# POWER.net
KiCad netlist of a schematic drawn in Altium Designer
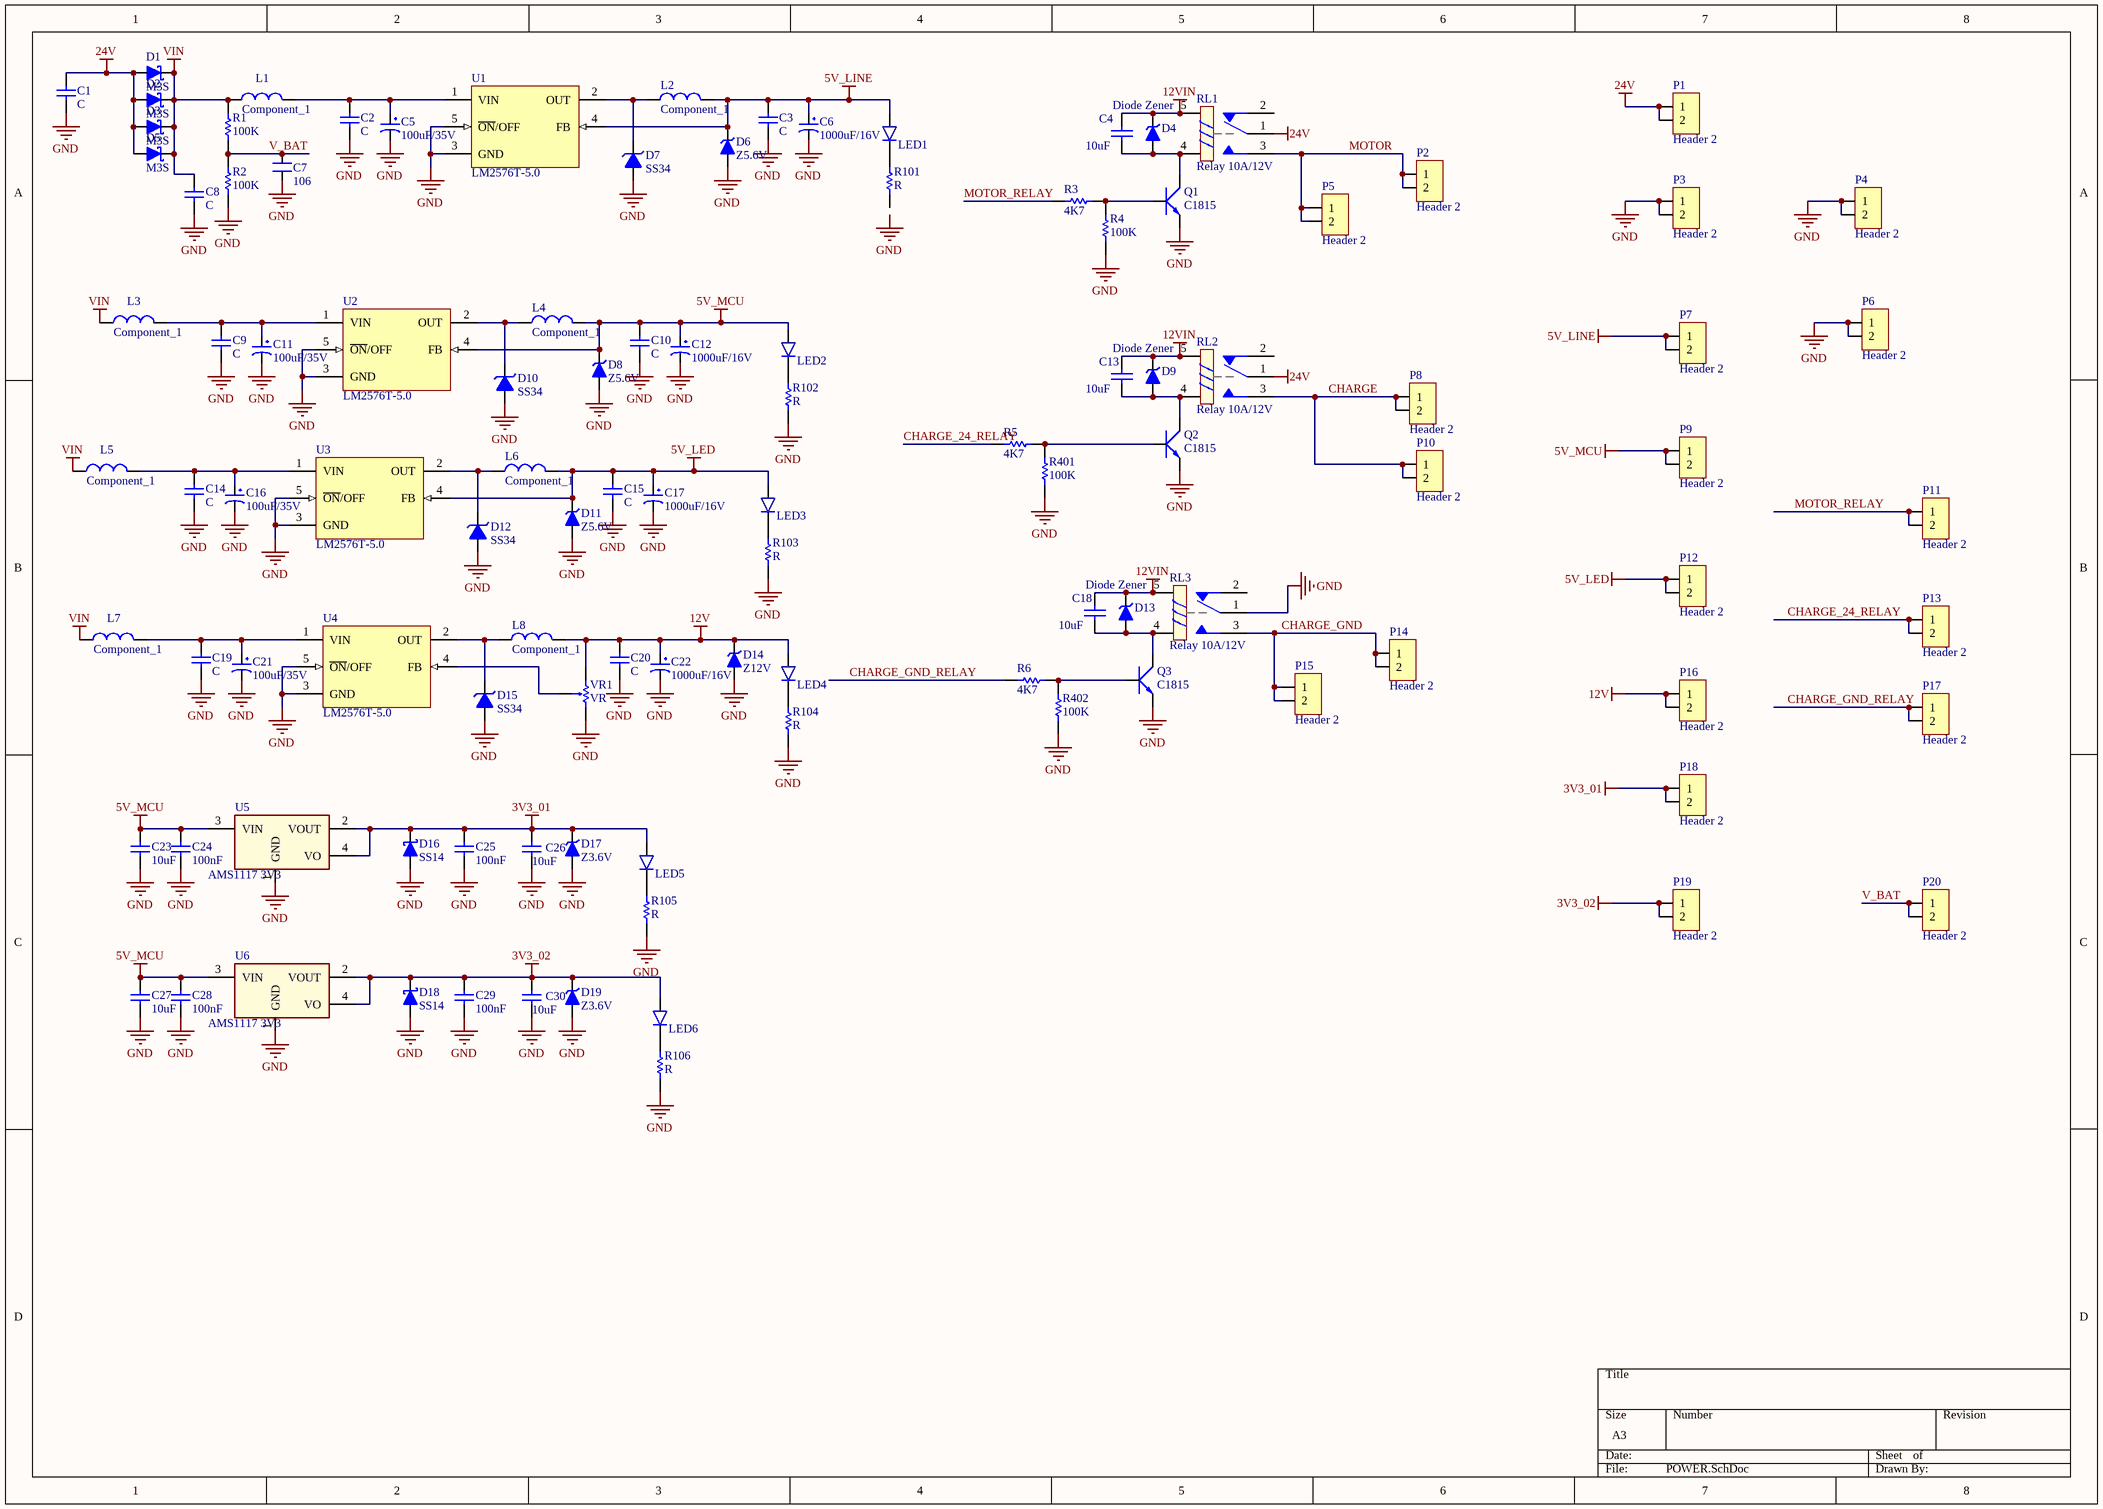
[diagram p0: POWER.SchDoc]

(export (version "E")
  (design (tool "Eeschema 10.0.6"))
  (components
    (comp (ref "C1")
      (value "C")
      (footprint "VARISTOR DISC 5MM/7MM")
      (description "Capacitor non-pol")
      (libsource (lib "BKIT4U_LIB") (part "Capacitor NP"))
    )
    (comp (ref "C2")
      (value "C")
      (footprint "C 104")
      (description "Capacitor non-pol")
      (libsource (lib "BKIT4U_LIB") (part "Capacitor NP"))
    )
    (comp (ref "C3")
      (value "C")
      (footprint "C 0805 (2012)")
      (description "Capacitor non-pol")
      (libsource (lib "BKIT4U_LIB") (part "Capacitor NP"))
    )
    (comp (ref "C4")
      (value "10uF")
      (footprint "C 0805 (2012)")
      (description "Non-polarized Capacitor")
      (fields (field (name "Comment") "Cap Non-pol") (field (name "PUBLISHER") "Altium Limited"))
      (libsource (lib "phong") (part "Cap Non-pol"))
    )
    (comp (ref "C5")
      (value "100uF/35V")
      (footprint "WCAP-PSHP 8x8.7x3.1")
      (description "Cap 100uF/35V - 470uF/16V")
      (libsource (lib "syhaunguyen") (part "CP3"))
    )
    (comp (ref "C6")
      (value "1000uF/16V")
      (footprint "WCAP-PSHP 8x8.7x3.1")
      (description "Cap 1000uF/16V - 220uF/50V")
      (libsource (lib "syhaunguyen") (part "CP4"))
    )
    (comp (ref "C7")
      (value "106")
      (footprint "R 0805 (2012)")
      (description "Cap np 104 => 105pF")
      (libsource (lib "syhaunguyen") (part "CN2"))
    )
    (comp (ref "C8")
      (value "C")
      (footprint "C 104")
      (description "Capacitor non-pol")
      (libsource (lib "BKIT4U_LIB") (part "Capacitor NP"))
    )
    (comp (ref "C9")
      (value "C")
      (footprint "C 104")
      (description "Capacitor non-pol")
      (libsource (lib "BKIT4U_LIB") (part "Capacitor NP"))
    )
    (comp (ref "C10")
      (value "C")
      (footprint "C 0805 (2012)")
      (description "Capacitor non-pol")
      (libsource (lib "BKIT4U_LIB") (part "Capacitor NP"))
    )
    (comp (ref "C11")
      (value "100uF/35V")
      (footprint "WCAP-PSHP 8x8.7x3.1")
      (description "Cap 100uF/35V - 470uF/16V")
      (libsource (lib "syhaunguyen") (part "CP3"))
    )
    (comp (ref "C12")
      (value "1000uF/16V")
      (footprint "WCAP-PSHP 8x8.7x3.1")
      (description "Cap 1000uF/16V - 220uF/50V")
      (libsource (lib "syhaunguyen") (part "CP4"))
    )
    (comp (ref "C13")
      (value "10uF")
      (footprint "C 0805 (2012)")
      (description "Non-polarized Capacitor")
      (fields (field (name "Comment") "Cap Non-pol") (field (name "PUBLISHER") "Altium Limited"))
      (libsource (lib "phong") (part "Cap Non-pol"))
    )
    (comp (ref "C14")
      (value "C")
      (footprint "C 104")
      (description "Capacitor non-pol")
      (libsource (lib "BKIT4U_LIB") (part "Capacitor NP"))
    )
    (comp (ref "C15")
      (value "C")
      (footprint "C 0805 (2012)")
      (description "Capacitor non-pol")
      (libsource (lib "BKIT4U_LIB") (part "Capacitor NP"))
    )
    (comp (ref "C16")
      (value "100uF/35V")
      (footprint "WCAP-PSHP 8x8.7x3.1")
      (description "Cap 100uF/35V - 470uF/16V")
      (libsource (lib "syhaunguyen") (part "CP3"))
    )
    (comp (ref "C17")
      (value "1000uF/16V")
      (footprint "WCAP-PSHP 8x8.7x3.1")
      (description "Cap 1000uF/16V - 220uF/50V")
      (libsource (lib "syhaunguyen") (part "CP4"))
    )
    (comp (ref "C18")
      (value "10uF")
      (footprint "C 0805 (2012)")
      (description "Non-polarized Capacitor")
      (fields (field (name "Comment") "Cap Non-pol") (field (name "PUBLISHER") "Altium Limited"))
      (libsource (lib "phong") (part "Cap Non-pol"))
    )
    (comp (ref "C19")
      (value "C")
      (footprint "C 104")
      (description "Capacitor non-pol")
      (libsource (lib "BKIT4U_LIB") (part "Capacitor NP"))
    )
    (comp (ref "C20")
      (value "C")
      (footprint "C 0805 (2012)")
      (description "Capacitor non-pol")
      (libsource (lib "BKIT4U_LIB") (part "Capacitor NP"))
    )
    (comp (ref "C21")
      (value "100uF/35V")
      (footprint "WCAP-PSHP 8x8.7x3.1")
      (description "Cap 100uF/35V - 470uF/16V")
      (libsource (lib "syhaunguyen") (part "CP3"))
    )
    (comp (ref "C22")
      (value "1000uF/16V")
      (footprint "WCAP-PSHP 8x8.7x3.1")
      (description "Cap 1000uF/16V - 220uF/50V")
      (libsource (lib "syhaunguyen") (part "CP4"))
    )
    (comp (ref "C23")
      (value "10uF")
      (footprint "C 0805 (2012)")
      (description "Capacitor non-pol")
      (libsource (lib "BKIT4U_LIB") (part "Capacitor NP"))
    )
    (comp (ref "C24")
      (value "100nF")
      (footprint "C 0805 (2012)")
      (description "Capacitor non-pol")
      (libsource (lib "BKIT4U_LIB") (part "Capacitor NP"))
    )
    (comp (ref "C25")
      (value "100nF")
      (footprint "C 0805 (2012)")
      (description "Capacitor non-pol")
      (libsource (lib "BKIT4U_LIB") (part "Capacitor NP"))
    )
    (comp (ref "C26")
      (value "10uF")
      (footprint "C 0805 (2012)")
      (description "Capacitor non-pol")
      (libsource (lib "BKIT4U_LIB") (part "Capacitor NP"))
    )
    (comp (ref "C27")
      (value "10uF")
      (footprint "C 0805 (2012)")
      (description "Capacitor non-pol")
      (libsource (lib "BKIT4U_LIB") (part "Capacitor NP"))
    )
    (comp (ref "C28")
      (value "100nF")
      (footprint "C 0805 (2012)")
      (description "Capacitor non-pol")
      (libsource (lib "BKIT4U_LIB") (part "Capacitor NP"))
    )
    (comp (ref "C29")
      (value "100nF")
      (footprint "C 0805 (2012)")
      (description "Capacitor non-pol")
      (libsource (lib "BKIT4U_LIB") (part "Capacitor NP"))
    )
    (comp (ref "C30")
      (value "10uF")
      (footprint "C 0805 (2012)")
      (description "Capacitor non-pol")
      (libsource (lib "BKIT4U_LIB") (part "Capacitor NP"))
    )
    (comp (ref "D1")
      (value "M3S")
      (footprint "DO-214AC (SMA)")
      (description "Schottky Diode")
      (fields (field (name "PUBLISHER") "Altium Limited"))
      (libsource (lib "BKIT4U_LIB") (part "Diode Schottky"))
    )
    (comp (ref "D2")
      (value "M3S")
      (footprint "DO-214AC (SMA)")
      (description "Schottky Diode")
      (fields (field (name "PUBLISHER") "Altium Limited"))
      (libsource (lib "BKIT4U_LIB") (part "Diode Schottky"))
    )
    (comp (ref "D3")
      (value "M3S")
      (footprint "DO-214AC (SMA)")
      (description "Schottky Diode")
      (fields (field (name "PUBLISHER") "Altium Limited"))
      (libsource (lib "BKIT4U_LIB") (part "Diode Schottky"))
    )
    (comp (ref "D4")
      (value "Diode Zener")
      (footprint "SOD-80")
      (description "Zener Diode")
      (fields (field (name "PUBLISHER") "Altium Limited"))
      (libsource (lib "BKIT4U_LIB") (part "Diode Zener"))
    )
    (comp (ref "D5")
      (value "M3S")
      (footprint "DO-214AC (SMA)")
      (description "Schottky Diode")
      (fields (field (name "PUBLISHER") "Altium Limited"))
      (libsource (lib "BKIT4U_LIB") (part "Diode Schottky"))
    )
    (comp (ref "D6")
      (value "Z5.6V")
      (footprint "SOD-80")
      (description "Zener Diode")
      (fields (field (name "PUBLISHER") "Altium Limited"))
      (libsource (lib "BKIT4U_LIB") (part "Diode Zener"))
    )
    (comp (ref "D7")
      (value "SS34")
      (footprint "DO-214AC (SMA) L")
      (libsource (lib "syhaunguyen") (part "Zener"))
    )
    (comp (ref "D8")
      (value "Z5.6V")
      (footprint "SOD-80")
      (description "Zener Diode")
      (fields (field (name "PUBLISHER") "Altium Limited"))
      (libsource (lib "BKIT4U_LIB") (part "Diode Zener"))
    )
    (comp (ref "D9")
      (value "Diode Zener")
      (footprint "SOD-80")
      (description "Zener Diode")
      (fields (field (name "PUBLISHER") "Altium Limited"))
      (libsource (lib "BKIT4U_LIB") (part "Diode Zener"))
    )
    (comp (ref "D10")
      (value "SS34")
      (footprint "DO-214AC (SMA) L")
      (libsource (lib "syhaunguyen") (part "Zener"))
    )
    (comp (ref "D11")
      (value "Z5.6V")
      (footprint "SOD-80")
      (description "Zener Diode")
      (fields (field (name "PUBLISHER") "Altium Limited"))
      (libsource (lib "BKIT4U_LIB") (part "Diode Zener"))
    )
    (comp (ref "D12")
      (value "SS34")
      (footprint "DO-214AC (SMA) L")
      (libsource (lib "syhaunguyen") (part "Zener"))
    )
    (comp (ref "D13")
      (value "Diode Zener")
      (footprint "SOD-80")
      (description "Zener Diode")
      (fields (field (name "PUBLISHER") "Altium Limited"))
      (libsource (lib "BKIT4U_LIB") (part "Diode Zener"))
    )
    (comp (ref "D14")
      (value "Z12V")
      (footprint "SOD-80")
      (description "Zener Diode")
      (fields (field (name "PUBLISHER") "Altium Limited"))
      (libsource (lib "BKIT4U_LIB") (part "Diode Zener"))
    )
    (comp (ref "D15")
      (value "SS34")
      (footprint "DO-214AC (SMA) L")
      (libsource (lib "syhaunguyen") (part "Zener"))
    )
    (comp (ref "D16")
      (value "SS14")
      (footprint "DO-214AC (SMA)")
      (description "Schottky Diode")
      (fields (field (name "PUBLISHER") "Altium Limited"))
      (libsource (lib "BKIT4U_LIB") (part "Diode Schottky"))
    )
    (comp (ref "D17")
      (value "Z3.6V")
      (footprint "SOD-80")
      (description "Zener Diode")
      (fields (field (name "PUBLISHER") "Altium Limited"))
      (libsource (lib "BKIT4U_LIB") (part "Diode Zener"))
    )
    (comp (ref "D18")
      (value "SS14")
      (footprint "DO-214AC (SMA)")
      (description "Schottky Diode")
      (fields (field (name "PUBLISHER") "Altium Limited"))
      (libsource (lib "BKIT4U_LIB") (part "Diode Schottky"))
    )
    (comp (ref "D19")
      (value "Z3.6V")
      (footprint "SOD-80")
      (description "Zener Diode")
      (fields (field (name "PUBLISHER") "Altium Limited"))
      (libsource (lib "BKIT4U_LIB") (part "Diode Zener"))
    )
    (comp (ref "L1")
      (value "Component_1")
      (footprint "1210")
      (libsource (lib "Integrated_Library1") (part "Component_1"))
    )
    (comp (ref "L2")
      (value "Component_1")
      (footprint "1210")
      (libsource (lib "Integrated_Library1") (part "Component_1"))
    )
    (comp (ref "L3")
      (value "Component_1")
      (footprint "1210")
      (libsource (lib "Integrated_Library1") (part "Component_1"))
    )
    (comp (ref "L4")
      (value "Component_1")
      (footprint "1210")
      (libsource (lib "Integrated_Library1") (part "Component_1"))
    )
    (comp (ref "L5")
      (value "Component_1")
      (footprint "1210")
      (libsource (lib "Integrated_Library1") (part "Component_1"))
    )
    (comp (ref "L6")
      (value "Component_1")
      (footprint "1210")
      (libsource (lib "Integrated_Library1") (part "Component_1"))
    )
    (comp (ref "L7")
      (value "Component_1")
      (footprint "1210")
      (libsource (lib "Integrated_Library1") (part "Component_1"))
    )
    (comp (ref "L8")
      (value "Component_1")
      (footprint "1210")
      (libsource (lib "Integrated_Library1") (part "Component_1"))
    )
    (comp (ref "LED1")
      (value "Led")
      (footprint "Led SMD 0805")
      (description "Typical LED")
      (libsource (lib "BKIT4U_LIB") (part "Led"))
    )
    (comp (ref "LED2")
      (value "Led")
      (footprint "Led SMD 0805")
      (description "Typical LED")
      (libsource (lib "BKIT4U_LIB") (part "Led"))
    )
    (comp (ref "LED3")
      (value "Led")
      (footprint "Led SMD 0805")
      (description "Typical LED")
      (libsource (lib "BKIT4U_LIB") (part "Led"))
    )
    (comp (ref "LED4")
      (value "Led")
      (footprint "Led SMD 0805")
      (description "Typical LED")
      (libsource (lib "BKIT4U_LIB") (part "Led"))
    )
    (comp (ref "LED5")
      (value "Led")
      (footprint "Led SMD 0805")
      (description "Typical LED")
      (libsource (lib "BKIT4U_LIB") (part "Led"))
    )
    (comp (ref "LED6")
      (value "Led")
      (footprint "Led SMD 0805")
      (description "Typical LED")
      (libsource (lib "BKIT4U_LIB") (part "Led"))
    )
    (comp (ref "P1")
      (value "Header 2")
      (footprint "HDR Domino 2")
      (description "Header, 2-Pin")
      (fields (field (name "PUBLISHER") "Altium Limited"))
      (libsource (lib "BKIT4U_LIB") (part "Header 2"))
    )
    (comp (ref "P2")
      (value "Header 2")
      (footprint "HDR Domino 2")
      (description "Header, 2-Pin")
      (fields (field (name "PUBLISHER") "Altium Limited"))
      (libsource (lib "BKIT4U_LIB") (part "Header 2"))
    )
    (comp (ref "P3")
      (value "Header 2")
      (footprint "HDR Domino 2")
      (description "Header, 2-Pin")
      (fields (field (name "PUBLISHER") "Altium Limited"))
      (libsource (lib "BKIT4U_LIB") (part "Header 2"))
    )
    (comp (ref "P4")
      (value "Header 2")
      (footprint "HDR Domino 2")
      (description "Header, 2-Pin")
      (fields (field (name "PUBLISHER") "Altium Limited"))
      (libsource (lib "BKIT4U_LIB") (part "Header 2"))
    )
    (comp (ref "P5")
      (value "Header 2")
      (footprint "HDR Domino 2")
      (description "Header, 2-Pin")
      (fields (field (name "PUBLISHER") "Altium Limited"))
      (libsource (lib "BKIT4U_LIB") (part "Header 2"))
    )
    (comp (ref "P6")
      (value "Header 2")
      (footprint "HDR Domino 2")
      (description "Header, 2-Pin")
      (fields (field (name "PUBLISHER") "Altium Limited"))
      (libsource (lib "BKIT4U_LIB") (part "Header 2"))
    )
    (comp (ref "P7")
      (value "Header 2")
      (footprint "HDR Domino 2")
      (description "Header, 2-Pin")
      (fields (field (name "PUBLISHER") "Altium Limited"))
      (libsource (lib "BKIT4U_LIB") (part "Header 2"))
    )
    (comp (ref "P8")
      (value "Header 2")
      (footprint "HDR Domino 2")
      (description "Header, 2-Pin")
      (fields (field (name "PUBLISHER") "Altium Limited"))
      (libsource (lib "BKIT4U_LIB") (part "Header 2"))
    )
    (comp (ref "P9")
      (value "Header 2")
      (footprint "HDR Domino 2")
      (description "Header, 2-Pin")
      (fields (field (name "PUBLISHER") "Altium Limited"))
      (libsource (lib "BKIT4U_LIB") (part "Header 2"))
    )
    (comp (ref "P10")
      (value "Header 2")
      (footprint "HDR Domino 2")
      (description "Header, 2-Pin")
      (fields (field (name "PUBLISHER") "Altium Limited"))
      (libsource (lib "BKIT4U_LIB") (part "Header 2"))
    )
    (comp (ref "P11")
      (value "Header 2")
      (footprint "HDR Domino 2")
      (description "Header, 2-Pin")
      (fields (field (name "PUBLISHER") "Altium Limited"))
      (libsource (lib "BKIT4U_LIB") (part "Header 2"))
    )
    (comp (ref "P12")
      (value "Header 2")
      (footprint "HDR Domino 2")
      (description "Header, 2-Pin")
      (fields (field (name "PUBLISHER") "Altium Limited"))
      (libsource (lib "BKIT4U_LIB") (part "Header 2"))
    )
    (comp (ref "P13")
      (value "Header 2")
      (footprint "HDR Domino 2")
      (description "Header, 2-Pin")
      (fields (field (name "PUBLISHER") "Altium Limited"))
      (libsource (lib "BKIT4U_LIB") (part "Header 2"))
    )
    (comp (ref "P14")
      (value "Header 2")
      (footprint "HDR Domino 2")
      (description "Header, 2-Pin")
      (fields (field (name "PUBLISHER") "Altium Limited"))
      (libsource (lib "BKIT4U_LIB") (part "Header 2"))
    )
    (comp (ref "P15")
      (value "Header 2")
      (footprint "HDR Domino 2")
      (description "Header, 2-Pin")
      (fields (field (name "PUBLISHER") "Altium Limited"))
      (libsource (lib "BKIT4U_LIB") (part "Header 2"))
    )
    (comp (ref "P16")
      (value "Header 2")
      (footprint "HDR Domino 2")
      (description "Header, 2-Pin")
      (fields (field (name "PUBLISHER") "Altium Limited"))
      (libsource (lib "BKIT4U_LIB") (part "Header 2"))
    )
    (comp (ref "P17")
      (value "Header 2")
      (footprint "HDR Domino 2")
      (description "Header, 2-Pin")
      (fields (field (name "PUBLISHER") "Altium Limited"))
      (libsource (lib "BKIT4U_LIB") (part "Header 2"))
    )
    (comp (ref "P18")
      (value "Header 2")
      (footprint "HDR Domino 2")
      (description "Header, 2-Pin")
      (fields (field (name "PUBLISHER") "Altium Limited"))
      (libsource (lib "BKIT4U_LIB") (part "Header 2"))
    )
    (comp (ref "P19")
      (value "Header 2")
      (footprint "HDR Domino 2")
      (description "Header, 2-Pin")
      (fields (field (name "PUBLISHER") "Altium Limited"))
      (libsource (lib "BKIT4U_LIB") (part "Header 2"))
    )
    (comp (ref "P20")
      (value "Header 2")
      (footprint "HDR Domino 2")
      (description "Header, 2-Pin")
      (fields (field (name "PUBLISHER") "Altium Limited"))
      (libsource (lib "BKIT4U_LIB") (part "Header 2"))
    )
    (comp (ref "Q1")
      (value "C1815")
      (footprint "SOT23B")
      (description "NPN 600mW, ECB")
      (libsource (lib "syhaunguyen") (part "C1815"))
    )
    (comp (ref "Q2")
      (value "C1815")
      (footprint "SOT23B")
      (description "NPN 600mW, ECB")
      (libsource (lib "syhaunguyen") (part "C1815"))
    )
    (comp (ref "Q3")
      (value "C1815")
      (footprint "SOT23B")
      (description "NPN 600mW, ECB")
      (libsource (lib "syhaunguyen") (part "C1815"))
    )
    (comp (ref "R1")
      (value "100K")
      (footprint "R 0805 (2012)")
      (description "Resistor")
      (fields (field (name "PUBLISHER") "Altium Limited"))
      (libsource (lib "BKIT4U_LIB") (part "Resistor"))
    )
    (comp (ref "R2")
      (value "100K")
      (footprint "R 0805 (2012)")
      (description "Resistor")
      (fields (field (name "PUBLISHER") "Altium Limited"))
      (libsource (lib "BKIT4U_LIB") (part "Resistor"))
    )
    (comp (ref "R3")
      (value "4K7")
      (footprint "R 0805 (2012)")
      (description "Resistor")
      (fields (field (name "PUBLISHER") "Altium Limited"))
      (libsource (lib "BKIT4U_LIB") (part "Resistor"))
    )
    (comp (ref "R4")
      (value "100K")
      (footprint "R 0805 (2012)")
      (description "Resistor")
      (fields (field (name "PUBLISHER") "Altium Limited"))
      (libsource (lib "BKIT4U_LIB") (part "Resistor"))
    )
    (comp (ref "R5")
      (value "4K7")
      (footprint "R 0805 (2012)")
      (description "Resistor")
      (fields (field (name "PUBLISHER") "Altium Limited"))
      (libsource (lib "BKIT4U_LIB") (part "Resistor"))
    )
    (comp (ref "R6")
      (value "4K7")
      (footprint "R 0805 (2012)")
      (description "Resistor")
      (fields (field (name "PUBLISHER") "Altium Limited"))
      (libsource (lib "BKIT4U_LIB") (part "Resistor"))
    )
    (comp (ref "R101")
      (value "R")
      (footprint "R 0805 (2012)")
      (description "Resistor")
      (fields (field (name "PUBLISHER") "Altium Limited"))
      (libsource (lib "BKIT4U_LIB") (part "Resistor"))
    )
    (comp (ref "R102")
      (value "R")
      (footprint "R 0805 (2012)")
      (description "Resistor")
      (fields (field (name "PUBLISHER") "Altium Limited"))
      (libsource (lib "BKIT4U_LIB") (part "Resistor"))
    )
    (comp (ref "R103")
      (value "R")
      (footprint "R 0805 (2012)")
      (description "Resistor")
      (fields (field (name "PUBLISHER") "Altium Limited"))
      (libsource (lib "BKIT4U_LIB") (part "Resistor"))
    )
    (comp (ref "R104")
      (value "R")
      (footprint "R 0805 (2012)")
      (description "Resistor")
      (fields (field (name "PUBLISHER") "Altium Limited"))
      (libsource (lib "BKIT4U_LIB") (part "Resistor"))
    )
    (comp (ref "R105")
      (value "R")
      (footprint "R 0805 (2012)")
      (description "Resistor")
      (fields (field (name "PUBLISHER") "Altium Limited"))
      (libsource (lib "BKIT4U_LIB") (part "Resistor"))
    )
    (comp (ref "R106")
      (value "R")
      (footprint "R 0805 (2012)")
      (description "Resistor")
      (fields (field (name "PUBLISHER") "Altium Limited"))
      (libsource (lib "BKIT4U_LIB") (part "Resistor"))
    )
    (comp (ref "R401")
      (value "100K")
      (footprint "R 0805 (2012)")
      (description "Resistor")
      (fields (field (name "PUBLISHER") "Altium Limited"))
      (libsource (lib "BKIT4U_LIB") (part "Resistor"))
    )
    (comp (ref "R402")
      (value "100K")
      (footprint "R 0805 (2012)")
      (description "Resistor")
      (fields (field (name "PUBLISHER") "Altium Limited"))
      (libsource (lib "BKIT4U_LIB") (part "Resistor"))
    )
    (comp (ref "RL1")
      (value "Relay 10A/12V")
      (footprint "RL_SPDT_10A")
      (description "Relay SPDT,10A - 12VDC 5 Pin")
      (libsource (lib "BKIT4U_LIB") (part "Relay 1"))
    )
    (comp (ref "RL2")
      (value "Relay 10A/12V")
      (footprint "RL_SPDT_10A")
      (description "Relay SPDT,10A - 12VDC 5 Pin")
      (libsource (lib "BKIT4U_LIB") (part "Relay 1"))
    )
    (comp (ref "RL3")
      (value "Relay 10A/12V")
      (footprint "RL_SPDT_10A")
      (description "Relay SPDT,10A - 12VDC 5 Pin")
      (libsource (lib "BKIT4U_LIB") (part "Relay 1"))
    )
    (comp (ref "U1")
      (value "LM2576T-5.0")
      (footprint "D2-PACK5")
      (description "SIMPLE SWITCHER; 3A Step-Down Voltage Regulator")
      (fields
        (field (name "MANUFACTURER") "National Semiconductor")
        (field (name "DIGIKEYPARTNUMBER") "LM2576T-5.0-ND")
        (field (name "PUBLISHER") "Altium Limited")
      )
      (libsource (lib "General IC") (part "LM2576T-5.0"))
    )
    (comp (ref "U2")
      (value "LM2576T-5.0")
      (footprint "D2-PACK5")
      (description "SIMPLE SWITCHER; 3A Step-Down Voltage Regulator")
      (fields
        (field (name "MANUFACTURER") "National Semiconductor")
        (field (name "DIGIKEYPARTNUMBER") "LM2576T-5.0-ND")
        (field (name "PUBLISHER") "Altium Limited")
      )
      (libsource (lib "General IC") (part "LM2576T-5.0"))
    )
    (comp (ref "U3")
      (value "LM2576T-5.0")
      (footprint "D2-PACK5")
      (description "SIMPLE SWITCHER; 3A Step-Down Voltage Regulator")
      (fields
        (field (name "MANUFACTURER") "National Semiconductor")
        (field (name "DIGIKEYPARTNUMBER") "LM2576T-5.0-ND")
        (field (name "PUBLISHER") "Altium Limited")
      )
      (libsource (lib "General IC") (part "LM2576T-5.0"))
    )
    (comp (ref "U4")
      (value "LM2576T-5.0")
      (footprint "D2-PACK5")
      (description "SIMPLE SWITCHER; 3A Step-Down Voltage Regulator")
      (fields
        (field (name "MANUFACTURER") "National Semiconductor")
        (field (name "DIGIKEYPARTNUMBER") "LM2576T-5.0-ND")
        (field (name "PUBLISHER") "Altium Limited")
      )
      (libsource (lib "General IC") (part "LM2576T-5.0"))
    )
    (comp (ref "U5")
      (value "AMS1117 3V3")
      (footprint "SOT-223")
      (description "1A LDO Voltage Regulator, ADJ or fixed 1.5/1.8/2.5/2.85/3.3/5V")
      (libsource (lib "BKIT4U_LIB") (part "AMS1117"))
    )
    (comp (ref "U6")
      (value "AMS1117 3V3")
      (footprint "SOT-223")
      (description "1A LDO Voltage Regulator, ADJ or fixed 1.5/1.8/2.5/2.85/3.3/5V")
      (libsource (lib "BKIT4U_LIB") (part "AMS1117"))
    )
    (comp (ref "VR1")
      (value "VR")
      (footprint "R VAR E")
      (description "Resistor Variable")
      (libsource (lib "chipfc_libs") (part "Resistor Variable"))
    )
  )
  (nets
    (net (code "1") (name "/CHARGE") (class "Default")
      (node (ref "P10") (pin "1") (pinfunction "1_1") (pintype "passive"))
      (node (ref "P10") (pin "2") (pinfunction "2_2") (pintype "passive"))
      (node (ref "P8") (pin "1") (pinfunction "1_1") (pintype "passive"))
      (node (ref "P8") (pin "2") (pinfunction "2_2") (pintype "passive"))
      (node (ref "RL2") (pin "3") (pinfunction "3_3") (pintype "passive"))
    )
    (net (code "2") (name "/CHARGE_24_RELAY") (class "Default")
      (node (ref "P13") (pin "1") (pinfunction "1_1") (pintype "passive"))
      (node (ref "P13") (pin "2") (pinfunction "2_2") (pintype "passive"))
      (node (ref "R5") (pin "1") (pinfunction "1_1") (pintype "passive"))
    )
    (net (code "3") (name "/CHARGE_GND") (class "Default")
      (node (ref "P14") (pin "1") (pinfunction "1_1") (pintype "passive"))
      (node (ref "P14") (pin "2") (pinfunction "2_2") (pintype "passive"))
      (node (ref "P15") (pin "1") (pinfunction "1_1") (pintype "passive"))
      (node (ref "P15") (pin "2") (pinfunction "2_2") (pintype "passive"))
      (node (ref "RL3") (pin "3") (pinfunction "3_3") (pintype "passive"))
    )
    (net (code "4") (name "/CHARGE_GND_RELAY") (class "Default")
      (node (ref "P17") (pin "1") (pinfunction "1_1") (pintype "passive"))
      (node (ref "P17") (pin "2") (pinfunction "2_2") (pintype "passive"))
      (node (ref "R6") (pin "1") (pinfunction "1_1") (pintype "passive"))
    )
    (net (code "5") (name "/MOTOR") (class "Default")
      (node (ref "P2") (pin "1") (pinfunction "1_1") (pintype "passive"))
      (node (ref "P2") (pin "2") (pinfunction "2_2") (pintype "passive"))
      (node (ref "P5") (pin "1") (pinfunction "1_1") (pintype "passive"))
      (node (ref "P5") (pin "2") (pinfunction "2_2") (pintype "passive"))
      (node (ref "RL1") (pin "3") (pinfunction "3_3") (pintype "passive"))
    )
    (net (code "6") (name "/MOTOR_RELAY") (class "Default")
      (node (ref "P11") (pin "1") (pinfunction "1_1") (pintype "passive"))
      (node (ref "P11") (pin "2") (pinfunction "2_2") (pintype "passive"))
      (node (ref "R3") (pin "1") (pinfunction "1_1") (pintype "passive"))
    )
    (net (code "7") (name "/V_BAT") (class "Default")
      (node (ref "C7") (pin "2") (pinfunction "2_2") (pintype "passive"))
      (node (ref "P20") (pin "1") (pinfunction "1_1") (pintype "passive"))
      (node (ref "P20") (pin "2") (pinfunction "2_2") (pintype "passive"))
      (node (ref "R1") (pin "2") (pinfunction "2_2") (pintype "passive"))
      (node (ref "R2") (pin "1") (pinfunction "1_1") (pintype "passive"))
    )
    (net (code "8") (name "3V3_01") (class "Default")
      (node (ref "C25") (pin "1") (pinfunction "1_1") (pintype "passive"))
      (node (ref "C26") (pin "1") (pinfunction "1_1") (pintype "passive"))
      (node (ref "D16") (pin "2") (pinfunction "K_2") (pintype "passive"))
      (node (ref "D17") (pin "2") (pinfunction "K_2") (pintype "passive"))
      (node (ref "LED5") (pin "1") (pinfunction "A_1") (pintype "passive"))
      (node (ref "P18") (pin "1") (pinfunction "1_1") (pintype "passive"))
      (node (ref "P18") (pin "2") (pinfunction "2_2") (pintype "passive"))
      (node (ref "U5") (pin "2") (pinfunction "VOUT_2") (pintype "passive"))
      (node (ref "U5") (pin "4") (pinfunction "VO_4") (pintype "passive"))
    )
    (net (code "9") (name "3V3_02") (class "Default")
      (node (ref "C29") (pin "1") (pinfunction "1_1") (pintype "passive"))
      (node (ref "C30") (pin "1") (pinfunction "1_1") (pintype "passive"))
      (node (ref "D18") (pin "2") (pinfunction "K_2") (pintype "passive"))
      (node (ref "D19") (pin "2") (pinfunction "K_2") (pintype "passive"))
      (node (ref "LED6") (pin "1") (pinfunction "A_1") (pintype "passive"))
      (node (ref "P19") (pin "1") (pinfunction "1_1") (pintype "passive"))
      (node (ref "P19") (pin "2") (pinfunction "2_2") (pintype "passive"))
      (node (ref "U6") (pin "2") (pinfunction "VOUT_2") (pintype "passive"))
      (node (ref "U6") (pin "4") (pinfunction "VO_4") (pintype "passive"))
    )
    (net (code "10") (name "5V_LED") (class "Default")
      (node (ref "C15") (pin "1") (pinfunction "1_1") (pintype "passive"))
      (node (ref "C17") (pin "1") (pinfunction "1_1") (pintype "passive"))
      (node (ref "D11") (pin "2") (pinfunction "K_2") (pintype "passive"))
      (node (ref "L6") (pin "2") (pinfunction "2_2") (pintype "passive"))
      (node (ref "LED3") (pin "1") (pinfunction "A_1") (pintype "passive"))
      (node (ref "P12") (pin "1") (pinfunction "1_1") (pintype "passive"))
      (node (ref "P12") (pin "2") (pinfunction "2_2") (pintype "passive"))
      (node (ref "U3") (pin "4") (pinfunction "FB_4") (pintype "input"))
    )
    (net (code "11") (name "5V_LINE") (class "Default")
      (node (ref "C3") (pin "1") (pinfunction "1_1") (pintype "passive"))
      (node (ref "C6") (pin "1") (pinfunction "1_1") (pintype "passive"))
      (node (ref "D6") (pin "2") (pinfunction "K_2") (pintype "passive"))
      (node (ref "L2") (pin "2") (pinfunction "2_2") (pintype "passive"))
      (node (ref "LED1") (pin "1") (pinfunction "A_1") (pintype "passive"))
      (node (ref "P7") (pin "1") (pinfunction "1_1") (pintype "passive"))
      (node (ref "P7") (pin "2") (pinfunction "2_2") (pintype "passive"))
      (node (ref "U1") (pin "4") (pinfunction "FB_4") (pintype "input"))
    )
    (net (code "12") (name "5V_MCU") (class "Default")
      (node (ref "C10") (pin "1") (pinfunction "1_1") (pintype "passive"))
      (node (ref "C12") (pin "1") (pinfunction "1_1") (pintype "passive"))
      (node (ref "C23") (pin "1") (pinfunction "1_1") (pintype "passive"))
      (node (ref "C24") (pin "1") (pinfunction "1_1") (pintype "passive"))
      (node (ref "C27") (pin "1") (pinfunction "1_1") (pintype "passive"))
      (node (ref "C28") (pin "1") (pinfunction "1_1") (pintype "passive"))
      (node (ref "D8") (pin "2") (pinfunction "K_2") (pintype "passive"))
      (node (ref "L4") (pin "2") (pinfunction "2_2") (pintype "passive"))
      (node (ref "LED2") (pin "1") (pinfunction "A_1") (pintype "passive"))
      (node (ref "P9") (pin "1") (pinfunction "1_1") (pintype "passive"))
      (node (ref "P9") (pin "2") (pinfunction "2_2") (pintype "passive"))
      (node (ref "U2") (pin "4") (pinfunction "FB_4") (pintype "input"))
      (node (ref "U5") (pin "3") (pinfunction "VIN_3") (pintype "power_in"))
      (node (ref "U6") (pin "3") (pinfunction "VIN_3") (pintype "power_in"))
    )
    (net (code "13") (name "12V") (class "Default")
      (node (ref "C20") (pin "1") (pinfunction "1_1") (pintype "passive"))
      (node (ref "C22") (pin "1") (pinfunction "1_1") (pintype "passive"))
      (node (ref "D14") (pin "2") (pinfunction "K_2") (pintype "passive"))
      (node (ref "L8") (pin "2") (pinfunction "2_2") (pintype "passive"))
      (node (ref "LED4") (pin "1") (pinfunction "A_1") (pintype "passive"))
      (node (ref "P16") (pin "1") (pinfunction "1_1") (pintype "passive"))
      (node (ref "P16") (pin "2") (pinfunction "2_2") (pintype "passive"))
      (node (ref "VR1") (pin "3") (pinfunction "3_3") (pintype "passive"))
    )
    (net (code "14") (name "12VIN") (class "Default")
      (node (ref "C13") (pin "2") (pinfunction "2_2") (pintype "passive"))
      (node (ref "C18") (pin "2") (pinfunction "2_2") (pintype "passive"))
      (node (ref "C4") (pin "2") (pinfunction "2_2") (pintype "passive"))
      (node (ref "D13") (pin "2") (pinfunction "K_2") (pintype "passive"))
      (node (ref "D4") (pin "2") (pinfunction "K_2") (pintype "passive"))
      (node (ref "D9") (pin "2") (pinfunction "K_2") (pintype "passive"))
      (node (ref "RL1") (pin "5") (pinfunction "5_5") (pintype "passive"))
      (node (ref "RL2") (pin "5") (pinfunction "5_5") (pintype "passive"))
      (node (ref "RL3") (pin "5") (pinfunction "5_5") (pintype "passive"))
    )
    (net (code "15") (name "24V") (class "Default")
      (node (ref "C1") (pin "1") (pinfunction "1_1") (pintype "passive"))
      (node (ref "D1") (pin "1") (pinfunction "A_1") (pintype "passive"))
      (node (ref "D2") (pin "1") (pinfunction "A_1") (pintype "passive"))
      (node (ref "D3") (pin "1") (pinfunction "A_1") (pintype "passive"))
      (node (ref "D5") (pin "1") (pinfunction "A_1") (pintype "passive"))
      (node (ref "P1") (pin "1") (pinfunction "1_1") (pintype "passive"))
      (node (ref "P1") (pin "2") (pinfunction "2_2") (pintype "passive"))
      (node (ref "RL1") (pin "1") (pinfunction "1_1") (pintype "passive"))
      (node (ref "RL2") (pin "1") (pinfunction "1_1") (pintype "passive"))
    )
    (net (code "16") (name "GND") (class "Default")
      (node (ref "C1") (pin "2") (pinfunction "2_2") (pintype "passive"))
      (node (ref "C10") (pin "2") (pinfunction "2_2") (pintype "passive"))
      (node (ref "C11") (pin "2") (pinfunction "2_2") (pintype "passive"))
      (node (ref "C12") (pin "2") (pinfunction "2_2") (pintype "passive"))
      (node (ref "C14") (pin "2") (pinfunction "2_2") (pintype "passive"))
      (node (ref "C15") (pin "2") (pinfunction "2_2") (pintype "passive"))
      (node (ref "C16") (pin "2") (pinfunction "2_2") (pintype "passive"))
      (node (ref "C17") (pin "2") (pinfunction "2_2") (pintype "passive"))
      (node (ref "C19") (pin "2") (pinfunction "2_2") (pintype "passive"))
      (node (ref "C2") (pin "2") (pinfunction "2_2") (pintype "passive"))
      (node (ref "C20") (pin "2") (pinfunction "2_2") (pintype "passive"))
      (node (ref "C21") (pin "2") (pinfunction "2_2") (pintype "passive"))
      (node (ref "C22") (pin "2") (pinfunction "2_2") (pintype "passive"))
      (node (ref "C23") (pin "2") (pinfunction "2_2") (pintype "passive"))
      (node (ref "C24") (pin "2") (pinfunction "2_2") (pintype "passive"))
      (node (ref "C25") (pin "2") (pinfunction "2_2") (pintype "passive"))
      (node (ref "C26") (pin "2") (pinfunction "2_2") (pintype "passive"))
      (node (ref "C27") (pin "2") (pinfunction "2_2") (pintype "passive"))
      (node (ref "C28") (pin "2") (pinfunction "2_2") (pintype "passive"))
      (node (ref "C29") (pin "2") (pinfunction "2_2") (pintype "passive"))
      (node (ref "C3") (pin "2") (pinfunction "2_2") (pintype "passive"))
      (node (ref "C30") (pin "2") (pinfunction "2_2") (pintype "passive"))
      (node (ref "C5") (pin "2") (pinfunction "2_2") (pintype "passive"))
      (node (ref "C6") (pin "2") (pinfunction "2_2") (pintype "passive"))
      (node (ref "C7") (pin "1") (pinfunction "1_1") (pintype "passive"))
      (node (ref "C8") (pin "2") (pinfunction "2_2") (pintype "passive"))
      (node (ref "C9") (pin "2") (pinfunction "2_2") (pintype "passive"))
      (node (ref "D10") (pin "1") (pinfunction "A_1") (pintype "passive"))
      (node (ref "D11") (pin "1") (pinfunction "A_1") (pintype "passive"))
      (node (ref "D12") (pin "1") (pinfunction "A_1") (pintype "passive"))
      (node (ref "D14") (pin "1") (pinfunction "A_1") (pintype "passive"))
      (node (ref "D15") (pin "1") (pinfunction "A_1") (pintype "passive"))
      (node (ref "D16") (pin "1") (pinfunction "A_1") (pintype "passive"))
      (node (ref "D17") (pin "1") (pinfunction "A_1") (pintype "passive"))
      (node (ref "D18") (pin "1") (pinfunction "A_1") (pintype "passive"))
      (node (ref "D19") (pin "1") (pinfunction "A_1") (pintype "passive"))
      (node (ref "D6") (pin "1") (pinfunction "A_1") (pintype "passive"))
      (node (ref "D7") (pin "1") (pinfunction "A_1") (pintype "passive"))
      (node (ref "D8") (pin "1") (pinfunction "A_1") (pintype "passive"))
      (node (ref "P3") (pin "1") (pinfunction "1_1") (pintype "passive"))
      (node (ref "P3") (pin "2") (pinfunction "2_2") (pintype "passive"))
      (node (ref "P4") (pin "1") (pinfunction "1_1") (pintype "passive"))
      (node (ref "P4") (pin "2") (pinfunction "2_2") (pintype "passive"))
      (node (ref "P6") (pin "1") (pinfunction "1_1") (pintype "passive"))
      (node (ref "P6") (pin "2") (pinfunction "2_2") (pintype "passive"))
      (node (ref "Q1") (pin "1") (pinfunction "E_1") (pintype "passive"))
      (node (ref "Q2") (pin "1") (pinfunction "E_1") (pintype "passive"))
      (node (ref "Q3") (pin "1") (pinfunction "E_1") (pintype "passive"))
      (node (ref "R102") (pin "1") (pinfunction "1_1") (pintype "passive"))
      (node (ref "R103") (pin "1") (pinfunction "1_1") (pintype "passive"))
      (node (ref "R104") (pin "1") (pinfunction "1_1") (pintype "passive"))
      (node (ref "R105") (pin "1") (pinfunction "1_1") (pintype "passive"))
      (node (ref "R106") (pin "1") (pinfunction "1_1") (pintype "passive"))
      (node (ref "R2") (pin "2") (pinfunction "2_2") (pintype "passive"))
      (node (ref "R4") (pin "1") (pinfunction "1_1") (pintype "passive"))
      (node (ref "R401") (pin "1") (pinfunction "1_1") (pintype "passive"))
      (node (ref "R402") (pin "1") (pinfunction "1_1") (pintype "passive"))
      (node (ref "RL3") (pin "1") (pinfunction "1_1") (pintype "passive"))
      (node (ref "U1") (pin "3") (pinfunction "GND_3") (pintype "power_in"))
      (node (ref "U1") (pin "5") (pinfunction "~{ON}/OFF_5") (pintype "input"))
      (node (ref "U2") (pin "3") (pinfunction "GND_3") (pintype "power_in"))
      (node (ref "U2") (pin "5") (pinfunction "~{ON}/OFF_5") (pintype "input"))
      (node (ref "U3") (pin "3") (pinfunction "GND_3") (pintype "power_in"))
      (node (ref "U3") (pin "5") (pinfunction "~{ON}/OFF_5") (pintype "input"))
      (node (ref "U4") (pin "3") (pinfunction "GND_3") (pintype "power_in"))
      (node (ref "U4") (pin "5") (pinfunction "~{ON}/OFF_5") (pintype "input"))
      (node (ref "U5") (pin "1") (pinfunction "GND_1") (pintype "passive"))
      (node (ref "U6") (pin "1") (pinfunction "GND_1") (pintype "passive"))
      (node (ref "VR1") (pin "1") (pinfunction "1_1") (pintype "passive"))
    )
    (net (code "17") (name "Net-(D4-A)") (class "Default")
      (node (ref "C4") (pin "1") (pinfunction "1_1") (pintype "passive"))
      (node (ref "D4") (pin "1") (pinfunction "A_1") (pintype "passive"))
      (node (ref "Q1") (pin "2") (pinfunction "C_2") (pintype "passive"))
      (node (ref "RL1") (pin "4") (pinfunction "4_4") (pintype "passive"))
    )
    (net (code "18") (name "Net-(D7-K)") (class "Default")
      (node (ref "D7") (pin "2") (pinfunction "K_2") (pintype "passive"))
      (node (ref "L2") (pin "1") (pinfunction "1_1") (pintype "passive"))
      (node (ref "U1") (pin "2") (pinfunction "OUT_2") (pintype "power_in"))
    )
    (net (code "19") (name "Net-(D9-A)") (class "Default")
      (node (ref "C13") (pin "1") (pinfunction "1_1") (pintype "passive"))
      (node (ref "D9") (pin "1") (pinfunction "A_1") (pintype "passive"))
      (node (ref "Q2") (pin "2") (pinfunction "C_2") (pintype "passive"))
      (node (ref "RL2") (pin "4") (pinfunction "4_4") (pintype "passive"))
    )
    (net (code "20") (name "Net-(D10-K)") (class "Default")
      (node (ref "D10") (pin "2") (pinfunction "K_2") (pintype "passive"))
      (node (ref "L4") (pin "1") (pinfunction "1_1") (pintype "passive"))
      (node (ref "U2") (pin "2") (pinfunction "OUT_2") (pintype "power_in"))
    )
    (net (code "21") (name "Net-(D12-K)") (class "Default")
      (node (ref "D12") (pin "2") (pinfunction "K_2") (pintype "passive"))
      (node (ref "L6") (pin "1") (pinfunction "1_1") (pintype "passive"))
      (node (ref "U3") (pin "2") (pinfunction "OUT_2") (pintype "power_in"))
    )
    (net (code "22") (name "Net-(D13-A)") (class "Default")
      (node (ref "C18") (pin "1") (pinfunction "1_1") (pintype "passive"))
      (node (ref "D13") (pin "1") (pinfunction "A_1") (pintype "passive"))
      (node (ref "Q3") (pin "2") (pinfunction "C_2") (pintype "passive"))
      (node (ref "RL3") (pin "4") (pinfunction "4_4") (pintype "passive"))
    )
    (net (code "23") (name "Net-(D15-K)") (class "Default")
      (node (ref "D15") (pin "2") (pinfunction "K_2") (pintype "passive"))
      (node (ref "L8") (pin "1") (pinfunction "1_1") (pintype "passive"))
      (node (ref "U4") (pin "2") (pinfunction "OUT_2") (pintype "power_in"))
    )
    (net (code "24") (name "Net-(LED1-K)") (class "Default")
      (node (ref "LED1") (pin "2") (pinfunction "K_2") (pintype "passive"))
      (node (ref "R101") (pin "2") (pinfunction "2_2") (pintype "passive"))
    )
    (net (code "25") (name "Net-(LED2-K)") (class "Default")
      (node (ref "LED2") (pin "2") (pinfunction "K_2") (pintype "passive"))
      (node (ref "R102") (pin "2") (pinfunction "2_2") (pintype "passive"))
    )
    (net (code "26") (name "Net-(LED3-K)") (class "Default")
      (node (ref "LED3") (pin "2") (pinfunction "K_2") (pintype "passive"))
      (node (ref "R103") (pin "2") (pinfunction "2_2") (pintype "passive"))
    )
    (net (code "27") (name "Net-(LED4-K)") (class "Default")
      (node (ref "LED4") (pin "2") (pinfunction "K_2") (pintype "passive"))
      (node (ref "R104") (pin "2") (pinfunction "2_2") (pintype "passive"))
    )
    (net (code "28") (name "Net-(LED5-K)") (class "Default")
      (node (ref "LED5") (pin "2") (pinfunction "K_2") (pintype "passive"))
      (node (ref "R105") (pin "2") (pinfunction "2_2") (pintype "passive"))
    )
    (net (code "29") (name "Net-(LED6-K)") (class "Default")
      (node (ref "LED6") (pin "2") (pinfunction "K_2") (pintype "passive"))
      (node (ref "R106") (pin "2") (pinfunction "2_2") (pintype "passive"))
    )
    (net (code "30") (name "Net-(Q1-B)") (class "Default")
      (node (ref "Q1") (pin "3") (pinfunction "B_3") (pintype "passive"))
      (node (ref "R3") (pin "2") (pinfunction "2_2") (pintype "passive"))
      (node (ref "R4") (pin "2") (pinfunction "2_2") (pintype "passive"))
    )
    (net (code "31") (name "Net-(Q2-B)") (class "Default")
      (node (ref "Q2") (pin "3") (pinfunction "B_3") (pintype "passive"))
      (node (ref "R401") (pin "2") (pinfunction "2_2") (pintype "passive"))
      (node (ref "R5") (pin "2") (pinfunction "2_2") (pintype "passive"))
    )
    (net (code "32") (name "Net-(Q3-B)") (class "Default")
      (node (ref "Q3") (pin "3") (pinfunction "B_3") (pintype "passive"))
      (node (ref "R402") (pin "2") (pinfunction "2_2") (pintype "passive"))
      (node (ref "R6") (pin "2") (pinfunction "2_2") (pintype "passive"))
    )
    (net (code "33") (name "Net-(U1-VIN)") (class "Default")
      (node (ref "C2") (pin "1") (pinfunction "1_1") (pintype "passive"))
      (node (ref "C5") (pin "1") (pinfunction "1_1") (pintype "passive"))
      (node (ref "L1") (pin "2") (pinfunction "2_2") (pintype "passive"))
      (node (ref "U1") (pin "1") (pinfunction "VIN_1") (pintype "power_in"))
    )
    (net (code "34") (name "Net-(U2-VIN)") (class "Default")
      (node (ref "C11") (pin "1") (pinfunction "1_1") (pintype "passive"))
      (node (ref "C9") (pin "1") (pinfunction "1_1") (pintype "passive"))
      (node (ref "L3") (pin "2") (pinfunction "2_2") (pintype "passive"))
      (node (ref "U2") (pin "1") (pinfunction "VIN_1") (pintype "power_in"))
    )
    (net (code "35") (name "Net-(U3-VIN)") (class "Default")
      (node (ref "C14") (pin "1") (pinfunction "1_1") (pintype "passive"))
      (node (ref "C16") (pin "1") (pinfunction "1_1") (pintype "passive"))
      (node (ref "L5") (pin "2") (pinfunction "2_2") (pintype "passive"))
      (node (ref "U3") (pin "1") (pinfunction "VIN_1") (pintype "power_in"))
    )
    (net (code "36") (name "Net-(U4-FB)") (class "Default")
      (node (ref "U4") (pin "4") (pinfunction "FB_4") (pintype "input"))
      (node (ref "VR1") (pin "2") (pinfunction "2_2") (pintype "passive"))
    )
    (net (code "37") (name "Net-(U4-VIN)") (class "Default")
      (node (ref "C19") (pin "1") (pinfunction "1_1") (pintype "passive"))
      (node (ref "C21") (pin "1") (pinfunction "1_1") (pintype "passive"))
      (node (ref "L7") (pin "2") (pinfunction "2_2") (pintype "passive"))
      (node (ref "U4") (pin "1") (pinfunction "VIN_1") (pintype "power_in"))
    )
    (net (code "38") (name "VIN") (class "Default")
      (node (ref "C8") (pin "1") (pinfunction "1_1") (pintype "passive"))
      (node (ref "D1") (pin "2") (pinfunction "K_2") (pintype "passive"))
      (node (ref "D2") (pin "2") (pinfunction "K_2") (pintype "passive"))
      (node (ref "D3") (pin "2") (pinfunction "K_2") (pintype "passive"))
      (node (ref "D5") (pin "2") (pinfunction "K_2") (pintype "passive"))
      (node (ref "L1") (pin "1") (pinfunction "1_1") (pintype "passive"))
      (node (ref "L3") (pin "1") (pinfunction "1_1") (pintype "passive"))
      (node (ref "L5") (pin "1") (pinfunction "1_1") (pintype "passive"))
      (node (ref "L7") (pin "1") (pinfunction "1_1") (pintype "passive"))
      (node (ref "R1") (pin "1") (pinfunction "1_1") (pintype "passive"))
    )
    (net (code "39") (name "unconnected-(R101-Pad1)") (class "Default")
      (node (ref "R101") (pin "1") (pinfunction "1_1") (pintype "passive"))
    )
    (net (code "40") (name "unconnected-(RL1-Pad2)") (class "Default")
      (node (ref "RL1") (pin "2") (pinfunction "2_2") (pintype "passive"))
    )
    (net (code "41") (name "unconnected-(RL2-Pad2)") (class "Default")
      (node (ref "RL2") (pin "2") (pinfunction "2_2") (pintype "passive"))
    )
    (net (code "42") (name "unconnected-(RL3-Pad2)") (class "Default")
      (node (ref "RL3") (pin "2") (pinfunction "2_2") (pintype "passive"))
    )
  )
)
